# FPGA_SUP_CFG.net
KiCad netlist of a schematic drawn in Altium Designer
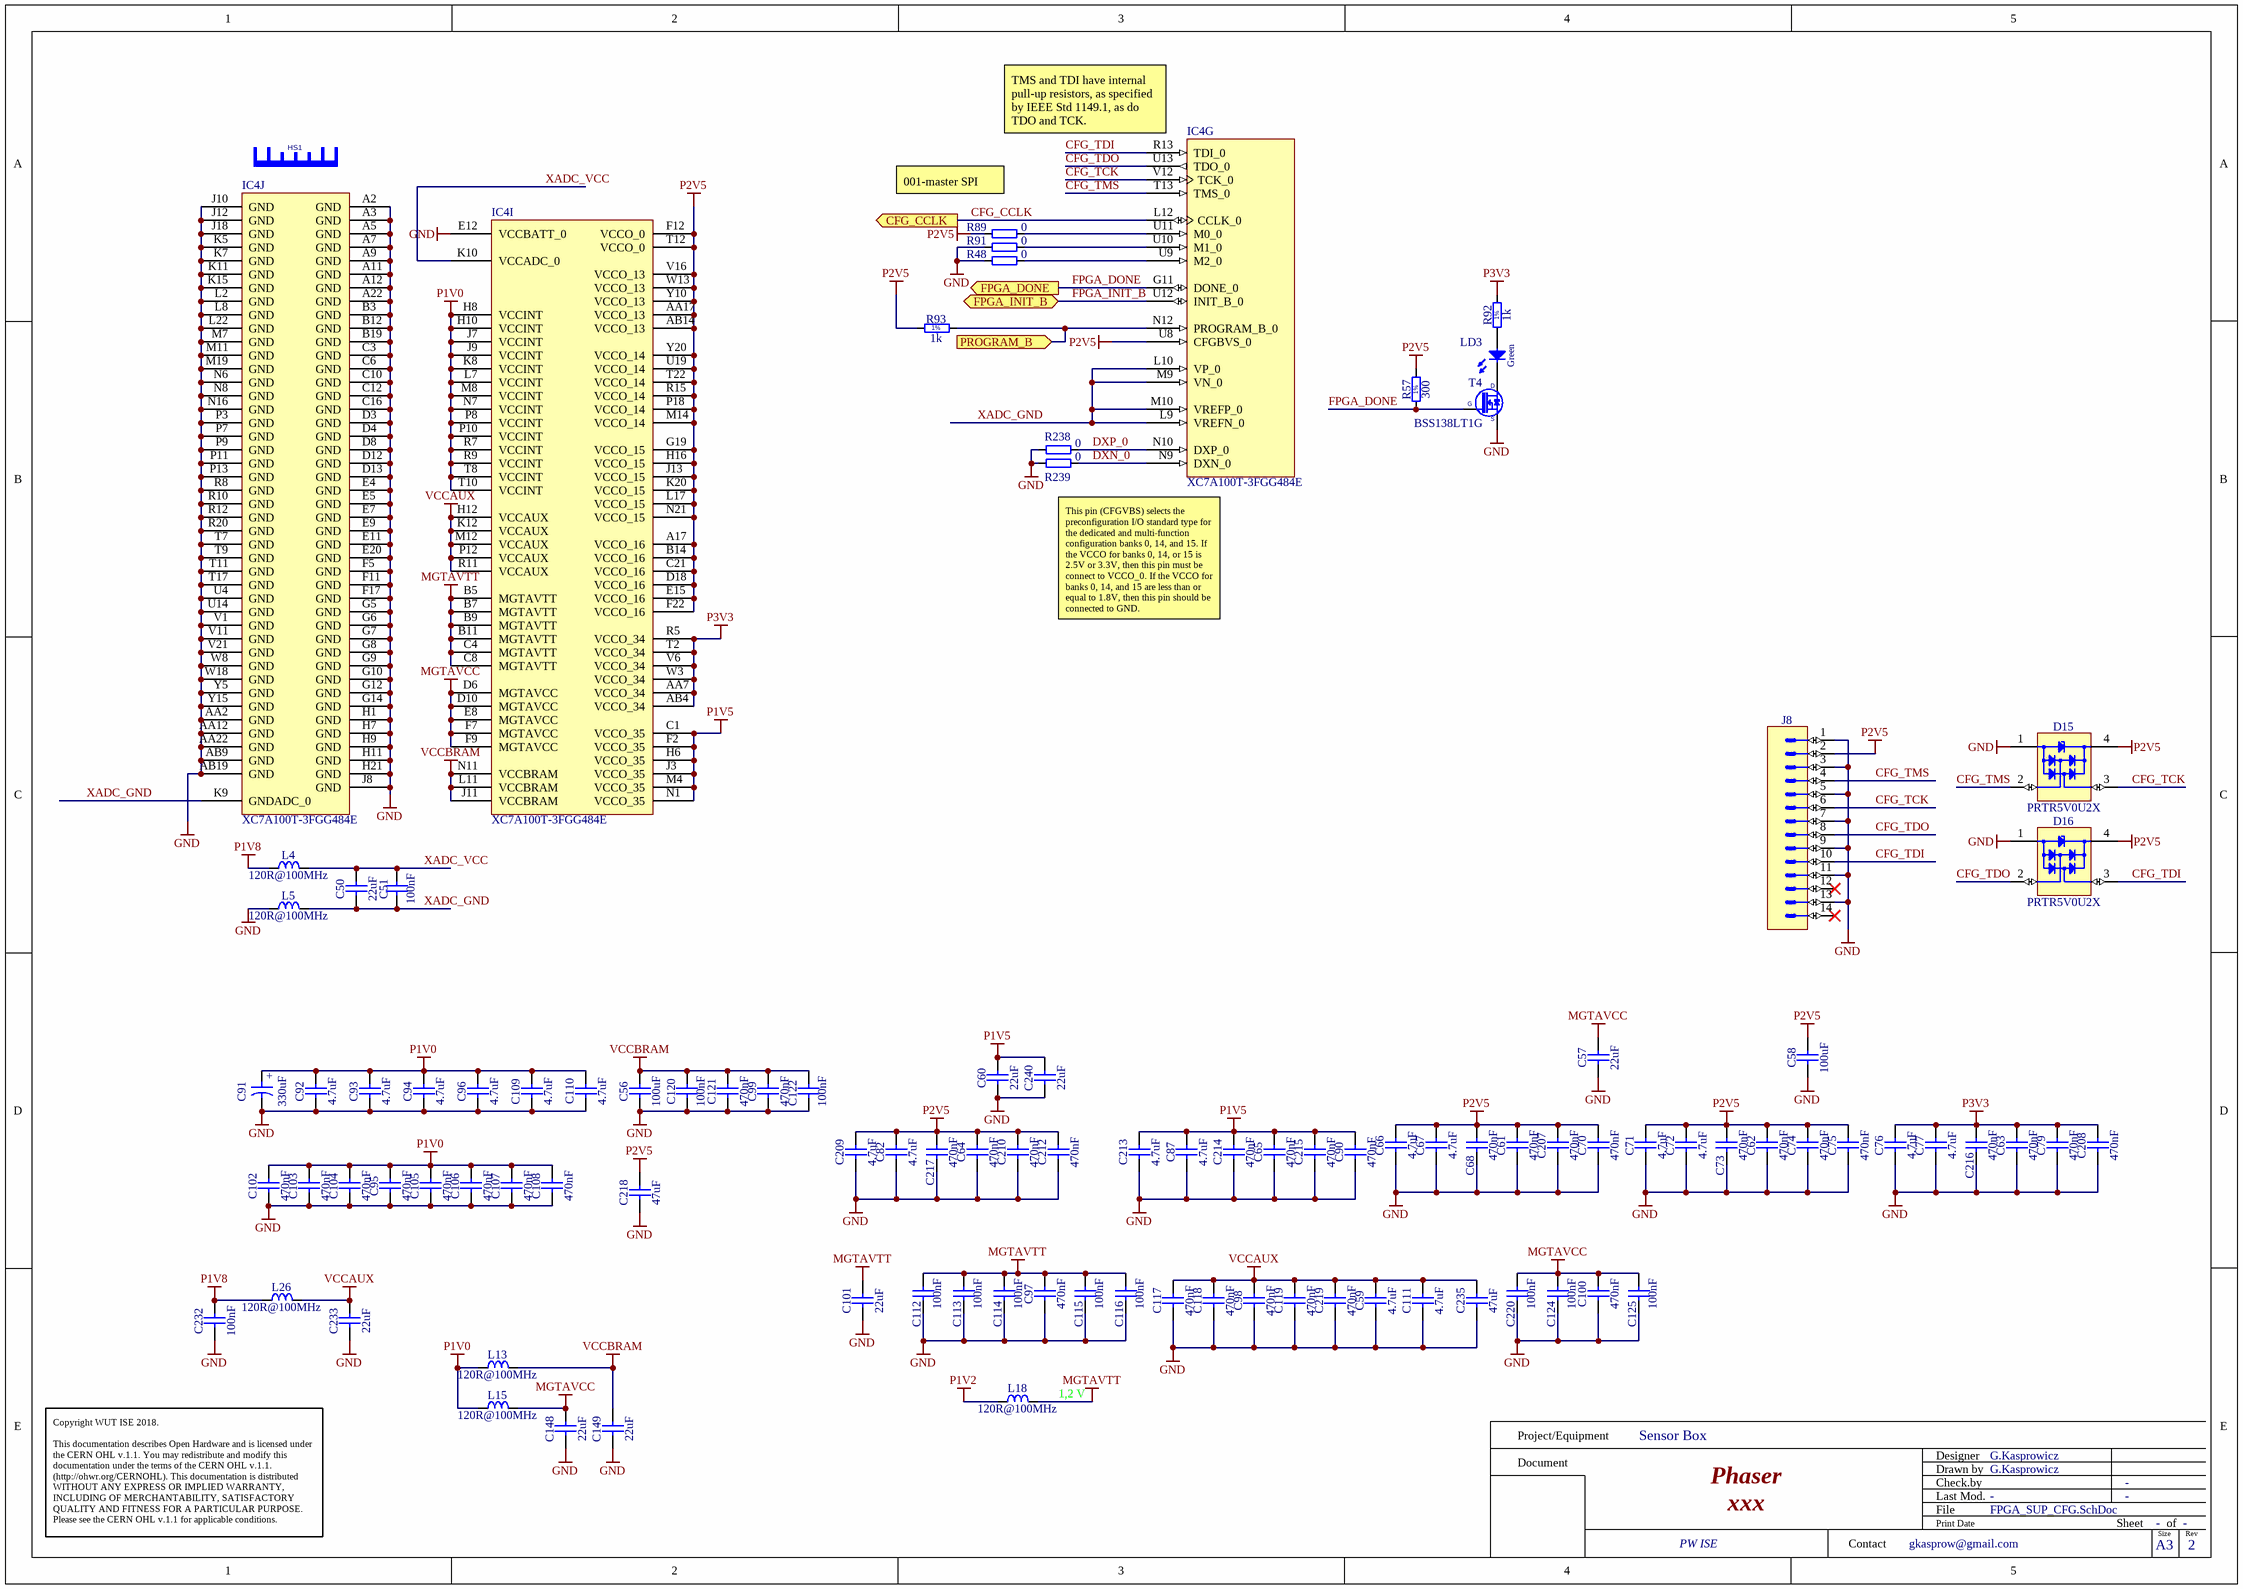
[diagram p0: FPGA_SUP_CFG.SchDoc]

(export (version "E")
  (design (tool "Eeschema 10.0.6"))
  (components
    (comp (ref "C50")
      (value "22uF")
      (footprint "CAPC1709X100N")
      (description "Non-polarised capacitor")
      (fields
        (field (name "PART NUMBER") "CC0603_22UF_6.3V_20%_X5R")
        (field (name "VOLTAGE") "6.3V")
        (field (name "AUTHOR") "CERN DEM JLC")
      )
      (libsource (lib "Capacitors") (part "Capacitor - non polarized"))
    )
    (comp (ref "C51")
      (value "100nF")
      (footprint "CAPC0603X33N")
      (description "Non-polarised capacitor")
      (fields
        (field (name "PART NUMBER") "CC0201_100NF_6.3V_10%_X5R")
        (field (name "VOLTAGE") "6.3V")
        (field (name "AUTHOR") "CERN DEM JLC")
      )
      (libsource (lib "Capacitors") (part "Capacitor - non polarized"))
    )
    (comp (ref "C56")
      (value "100uF")
      (footprint "CAPC3225X270N")
      (description "Non-polarised capacitor")
      (fields
        (field (name "PART NUMBER") "CC1210_100UF_6.3V_20%_X5R")
        (field (name "VOLTAGE") "6.3V")
        (field (name "AUTHOR") "CERN DEM JLC")
      )
      (libsource (lib "Capacitors") (part "Capacitor - non polarized"))
    )
    (comp (ref "C57")
      (value "22uF")
      (footprint "CAPC1709X100N")
      (description "Non-polarised capacitor")
      (fields
        (field (name "PART NUMBER") "CC0603_22UF_6.3V_20%_X5R")
        (field (name "VOLTAGE") "6.3V")
        (field (name "AUTHOR") "CERN DEM JLC")
      )
      (libsource (lib "Capacitors") (part "Capacitor - non polarized"))
    )
    (comp (ref "C58")
      (value "100uF")
      (footprint "CAPC3225X270N")
      (description "Non-polarised capacitor")
      (fields
        (field (name "PART NUMBER") "CC1210_100UF_6.3V_20%_X5R")
        (field (name "VOLTAGE") "6.3V")
        (field (name "AUTHOR") "CERN DEM JLC")
      )
      (libsource (lib "Capacitors") (part "Capacitor - non polarized"))
    )
    (comp (ref "C59")
      (value "4.7uF")
      (footprint "CAPC2012X135N")
      (description "Non-polarised capacitor")
      (fields
        (field (name "MANUFACTURER") "GENERIC")
        (field (name "PART NUMBER") "CC0805_4.7UF_10V_10%_X5R")
        (field (name "AUTHOR") "CERN DEM JLC")
      )
      (libsource (lib "Capacitors") (part "Capacitor - non polarized"))
    )
    (comp (ref "C60")
      (value "22uF")
      (footprint "CAPC1709X100N")
      (description "Non-polarised capacitor")
      (fields
        (field (name "PART NUMBER") "CC0603_22UF_6.3V_20%_X5R")
        (field (name "VOLTAGE") "6.3V")
        (field (name "AUTHOR") "CERN DEM JLC")
      )
      (libsource (lib "Capacitors") (part "Capacitor - non polarized"))
    )
    (comp (ref "C61")
      (value "470nF")
      (footprint "CAPC0603X33N")
      (description "Non-polarised capacitor")
      (fields
        (field (name "PART NUMBER") "CC0201_470NF_4V_20%_X5R")
        (field (name "VOLTAGE") "4V")
        (field (name "AUTHOR") "CERN DEM JLC")
      )
      (libsource (lib "Capacitors") (part "Capacitor - non polarized"))
    )
    (comp (ref "C62")
      (value "470nF")
      (footprint "CAPC0603X33N")
      (description "Non-polarised capacitor")
      (fields
        (field (name "PART NUMBER") "CC0201_470NF_4V_20%_X5R")
        (field (name "VOLTAGE") "4V")
        (field (name "AUTHOR") "CERN DEM JLC")
      )
      (libsource (lib "Capacitors") (part "Capacitor - non polarized"))
    )
    (comp (ref "C63")
      (value "470nF")
      (footprint "CAPC0603X33N")
      (description "Non-polarised capacitor")
      (fields
        (field (name "PART NUMBER") "CC0201_470NF_4V_20%_X5R")
        (field (name "VOLTAGE") "4V")
        (field (name "AUTHOR") "CERN DEM JLC")
      )
      (libsource (lib "Capacitors") (part "Capacitor - non polarized"))
    )
    (comp (ref "C64")
      (value "470nF")
      (footprint "CAPC0603X33N")
      (description "Non-polarised capacitor")
      (fields
        (field (name "PART NUMBER") "CC0201_470NF_4V_20%_X5R")
        (field (name "VOLTAGE") "4V")
        (field (name "AUTHOR") "CERN DEM JLC")
      )
      (libsource (lib "Capacitors") (part "Capacitor - non polarized"))
    )
    (comp (ref "C65")
      (value "470nF")
      (footprint "CAPC0603X33N")
      (description "Non-polarised capacitor")
      (fields
        (field (name "PART NUMBER") "CC0201_470NF_4V_20%_X5R")
        (field (name "VOLTAGE") "4V")
        (field (name "AUTHOR") "CERN DEM JLC")
      )
      (libsource (lib "Capacitors") (part "Capacitor - non polarized"))
    )
    (comp (ref "C66")
      (value "4.7uF")
      (footprint "CAPC2012X135N")
      (description "Non-polarised capacitor")
      (fields
        (field (name "MANUFACTURER") "GENERIC")
        (field (name "PART NUMBER") "CC0805_4.7UF_10V_10%_X5R")
        (field (name "AUTHOR") "CERN DEM JLC")
      )
      (libsource (lib "Capacitors") (part "Capacitor - non polarized"))
    )
    (comp (ref "C67")
      (value "4.7uF")
      (footprint "CAPC2012X135N")
      (description "Non-polarised capacitor")
      (fields
        (field (name "MANUFACTURER") "GENERIC")
        (field (name "PART NUMBER") "CC0805_4.7UF_10V_10%_X5R")
        (field (name "AUTHOR") "CERN DEM JLC")
      )
      (libsource (lib "Capacitors") (part "Capacitor - non polarized"))
    )
    (comp (ref "C68")
      (value "470nF")
      (footprint "CAPC0603X33N")
      (description "Non-polarised capacitor")
      (fields
        (field (name "PART NUMBER") "CC0201_470NF_4V_20%_X5R")
        (field (name "VOLTAGE") "4V")
        (field (name "AUTHOR") "CERN DEM JLC")
      )
      (libsource (lib "Capacitors") (part "Capacitor - non polarized"))
    )
    (comp (ref "C70")
      (value "470nF")
      (footprint "CAPC0603X33N")
      (description "Non-polarised capacitor")
      (fields
        (field (name "PART NUMBER") "CC0201_470NF_4V_20%_X5R")
        (field (name "VOLTAGE") "4V")
        (field (name "AUTHOR") "CERN DEM JLC")
      )
      (libsource (lib "Capacitors") (part "Capacitor - non polarized"))
    )
    (comp (ref "C71")
      (value "4.7uF")
      (footprint "CAPC2012X135N")
      (description "Non-polarised capacitor")
      (fields
        (field (name "MANUFACTURER") "GENERIC")
        (field (name "PART NUMBER") "CC0805_4.7UF_10V_10%_X5R")
        (field (name "AUTHOR") "CERN DEM JLC")
      )
      (libsource (lib "Capacitors") (part "Capacitor - non polarized"))
    )
    (comp (ref "C72")
      (value "4.7uF")
      (footprint "CAPC2012X135N")
      (description "Non-polarised capacitor")
      (fields
        (field (name "MANUFACTURER") "GENERIC")
        (field (name "PART NUMBER") "CC0805_4.7UF_10V_10%_X5R")
        (field (name "AUTHOR") "CERN DEM JLC")
      )
      (libsource (lib "Capacitors") (part "Capacitor - non polarized"))
    )
    (comp (ref "C73")
      (value "470nF")
      (footprint "CAPC0603X33N")
      (description "Non-polarised capacitor")
      (fields
        (field (name "PART NUMBER") "CC0201_470NF_4V_20%_X5R")
        (field (name "VOLTAGE") "4V")
        (field (name "AUTHOR") "CERN DEM JLC")
      )
      (libsource (lib "Capacitors") (part "Capacitor - non polarized"))
    )
    (comp (ref "C74")
      (value "470nF")
      (footprint "CAPC0603X33N")
      (description "Non-polarised capacitor")
      (fields
        (field (name "PART NUMBER") "CC0201_470NF_4V_20%_X5R")
        (field (name "VOLTAGE") "4V")
        (field (name "AUTHOR") "CERN DEM JLC")
      )
      (libsource (lib "Capacitors") (part "Capacitor - non polarized"))
    )
    (comp (ref "C75")
      (value "470nF")
      (footprint "CAPC0603X33N")
      (description "Non-polarised capacitor")
      (fields
        (field (name "PART NUMBER") "CC0201_470NF_4V_20%_X5R")
        (field (name "VOLTAGE") "4V")
        (field (name "AUTHOR") "CERN DEM JLC")
      )
      (libsource (lib "Capacitors") (part "Capacitor - non polarized"))
    )
    (comp (ref "C76")
      (value "4.7uF")
      (footprint "CAPC2012X135N")
      (description "Non-polarised capacitor")
      (fields
        (field (name "MANUFACTURER") "GENERIC")
        (field (name "PART NUMBER") "CC0805_4.7UF_10V_10%_X5R")
        (field (name "AUTHOR") "CERN DEM JLC")
      )
      (libsource (lib "Capacitors") (part "Capacitor - non polarized"))
    )
    (comp (ref "C77")
      (value "4.7uF")
      (footprint "CAPC2012X135N")
      (description "Non-polarised capacitor")
      (fields
        (field (name "MANUFACTURER") "GENERIC")
        (field (name "PART NUMBER") "CC0805_4.7UF_10V_10%_X5R")
        (field (name "AUTHOR") "CERN DEM JLC")
      )
      (libsource (lib "Capacitors") (part "Capacitor - non polarized"))
    )
    (comp (ref "C79")
      (value "470nF")
      (footprint "CAPC0603X33N")
      (description "Non-polarised capacitor")
      (fields
        (field (name "PART NUMBER") "CC0201_470NF_4V_20%_X5R")
        (field (name "VOLTAGE") "4V")
        (field (name "AUTHOR") "CERN DEM JLC")
      )
      (libsource (lib "Capacitors") (part "Capacitor - non polarized"))
    )
    (comp (ref "C82")
      (value "4.7uF")
      (footprint "CAPC2012X135N")
      (description "Non-polarised capacitor")
      (fields
        (field (name "MANUFACTURER") "GENERIC")
        (field (name "PART NUMBER") "CC0805_4.7UF_10V_10%_X5R")
        (field (name "AUTHOR") "CERN DEM JLC")
      )
      (libsource (lib "Capacitors") (part "Capacitor - non polarized"))
    )
    (comp (ref "C87")
      (value "4.7uF")
      (footprint "CAPC2012X135N")
      (description "Non-polarised capacitor")
      (fields
        (field (name "MANUFACTURER") "GENERIC")
        (field (name "PART NUMBER") "CC0805_4.7UF_10V_10%_X5R")
        (field (name "AUTHOR") "CERN DEM JLC")
      )
      (libsource (lib "Capacitors") (part "Capacitor - non polarized"))
    )
    (comp (ref "C90")
      (value "470nF")
      (footprint "CAPC0603X33N")
      (description "Non-polarised capacitor")
      (fields
        (field (name "PART NUMBER") "CC0201_470NF_4V_20%_X5R")
        (field (name "VOLTAGE") "4V")
        (field (name "AUTHOR") "CERN DEM JLC")
      )
      (libsource (lib "Capacitors") (part "Capacitor - non polarized"))
    )
    (comp (ref "C91")
      (value "330uF")
      (footprint "CAPMP7343X190N")
      (description "Polarised capacitor")
      (fields
        (field (name "PART NUMBER") "CTE7343-19_330UF_2.5V_20%_LESR0025_KEMET_T520")
        (field (name "VOLTAGE") "2.5V")
        (field (name "AUTHOR") "CERN DEM MR")
      )
      (libsource (lib "Capacitors") (part "Capacitor - polarized"))
    )
    (comp (ref "C92")
      (value "4.7uF")
      (footprint "CAPC2012X135N")
      (description "Non-polarised capacitor")
      (fields
        (field (name "MANUFACTURER") "GENERIC")
        (field (name "PART NUMBER") "CC0805_4.7UF_10V_10%_X5R")
        (field (name "AUTHOR") "CERN DEM JLC")
      )
      (libsource (lib "Capacitors") (part "Capacitor - non polarized"))
    )
    (comp (ref "C93")
      (value "4.7uF")
      (footprint "CAPC2012X135N")
      (description "Non-polarised capacitor")
      (fields
        (field (name "MANUFACTURER") "GENERIC")
        (field (name "PART NUMBER") "CC0805_4.7UF_10V_10%_X5R")
        (field (name "AUTHOR") "CERN DEM JLC")
      )
      (libsource (lib "Capacitors") (part "Capacitor - non polarized"))
    )
    (comp (ref "C94")
      (value "4.7uF")
      (footprint "CAPC2012X135N")
      (description "Non-polarised capacitor")
      (fields
        (field (name "MANUFACTURER") "GENERIC")
        (field (name "PART NUMBER") "CC0805_4.7UF_10V_10%_X5R")
        (field (name "AUTHOR") "CERN DEM JLC")
      )
      (libsource (lib "Capacitors") (part "Capacitor - non polarized"))
    )
    (comp (ref "C95")
      (value "470nF")
      (footprint "CAPC0603X33N")
      (description "Non-polarised capacitor")
      (fields
        (field (name "PART NUMBER") "CC0201_470NF_4V_20%_X5R")
        (field (name "VOLTAGE") "4V")
        (field (name "AUTHOR") "CERN DEM JLC")
      )
      (libsource (lib "Capacitors") (part "Capacitor - non polarized"))
    )
    (comp (ref "C96")
      (value "4.7uF")
      (footprint "CAPC2012X135N")
      (description "Non-polarised capacitor")
      (fields
        (field (name "MANUFACTURER") "GENERIC")
        (field (name "PART NUMBER") "CC0805_4.7UF_10V_10%_X5R")
        (field (name "AUTHOR") "CERN DEM JLC")
      )
      (libsource (lib "Capacitors") (part "Capacitor - non polarized"))
    )
    (comp (ref "C97")
      (value "470nF")
      (footprint "CAPC0603X33N")
      (description "Non-polarised capacitor")
      (fields
        (field (name "PART NUMBER") "CC0201_470NF_4V_20%_X5R")
        (field (name "VOLTAGE") "4V")
        (field (name "AUTHOR") "CERN DEM JLC")
      )
      (libsource (lib "Capacitors") (part "Capacitor - non polarized"))
    )
    (comp (ref "C98")
      (value "470nF")
      (footprint "CAPC0603X33N")
      (description "Non-polarised capacitor")
      (fields
        (field (name "PART NUMBER") "CC0201_470NF_4V_20%_X5R")
        (field (name "VOLTAGE") "4V")
        (field (name "AUTHOR") "CERN DEM JLC")
      )
      (libsource (lib "Capacitors") (part "Capacitor - non polarized"))
    )
    (comp (ref "C99")
      (value "470nF")
      (footprint "CAPC0603X33N")
      (description "Non-polarised capacitor")
      (fields
        (field (name "PART NUMBER") "CC0201_470NF_4V_20%_X5R")
        (field (name "VOLTAGE") "4V")
        (field (name "AUTHOR") "CERN DEM JLC")
      )
      (libsource (lib "Capacitors") (part "Capacitor - non polarized"))
    )
    (comp (ref "C100")
      (value "470nF")
      (footprint "CAPC0603X33N")
      (description "Non-polarised capacitor")
      (fields
        (field (name "PART NUMBER") "CC0201_470NF_4V_20%_X5R")
        (field (name "VOLTAGE") "4V")
        (field (name "AUTHOR") "CERN DEM JLC")
      )
      (libsource (lib "Capacitors") (part "Capacitor - non polarized"))
    )
    (comp (ref "C101")
      (value "22uF")
      (footprint "CAPC1709X100N")
      (description "Non-polarised capacitor")
      (fields
        (field (name "PART NUMBER") "CC0603_22UF_6.3V_20%_X5R")
        (field (name "VOLTAGE") "6.3V")
        (field (name "AUTHOR") "CERN DEM JLC")
      )
      (libsource (lib "Capacitors") (part "Capacitor - non polarized"))
    )
    (comp (ref "C102")
      (value "470nF")
      (footprint "CAPC0603X33N")
      (description "Non-polarised capacitor")
      (fields
        (field (name "PART NUMBER") "CC0201_470NF_4V_20%_X5R")
        (field (name "VOLTAGE") "4V")
        (field (name "AUTHOR") "CERN DEM JLC")
      )
      (libsource (lib "Capacitors") (part "Capacitor - non polarized"))
    )
    (comp (ref "C103")
      (value "470nF")
      (footprint "CAPC0603X33N")
      (description "Non-polarised capacitor")
      (fields
        (field (name "PART NUMBER") "CC0201_470NF_4V_20%_X5R")
        (field (name "VOLTAGE") "4V")
        (field (name "AUTHOR") "CERN DEM JLC")
      )
      (libsource (lib "Capacitors") (part "Capacitor - non polarized"))
    )
    (comp (ref "C104")
      (value "470nF")
      (footprint "CAPC0603X33N")
      (description "Non-polarised capacitor")
      (fields
        (field (name "PART NUMBER") "CC0201_470NF_4V_20%_X5R")
        (field (name "VOLTAGE") "4V")
        (field (name "AUTHOR") "CERN DEM JLC")
      )
      (libsource (lib "Capacitors") (part "Capacitor - non polarized"))
    )
    (comp (ref "C105")
      (value "470nF")
      (footprint "CAPC0603X33N")
      (description "Non-polarised capacitor")
      (fields
        (field (name "PART NUMBER") "CC0201_470NF_4V_20%_X5R")
        (field (name "VOLTAGE") "4V")
        (field (name "AUTHOR") "CERN DEM JLC")
      )
      (libsource (lib "Capacitors") (part "Capacitor - non polarized"))
    )
    (comp (ref "C106")
      (value "470nF")
      (footprint "CAPC0603X33N")
      (description "Non-polarised capacitor")
      (fields
        (field (name "PART NUMBER") "CC0201_470NF_4V_20%_X5R")
        (field (name "VOLTAGE") "4V")
        (field (name "AUTHOR") "CERN DEM JLC")
      )
      (libsource (lib "Capacitors") (part "Capacitor - non polarized"))
    )
    (comp (ref "C107")
      (value "470nF")
      (footprint "CAPC0603X33N")
      (description "Non-polarised capacitor")
      (fields
        (field (name "PART NUMBER") "CC0201_470NF_4V_20%_X5R")
        (field (name "VOLTAGE") "4V")
        (field (name "AUTHOR") "CERN DEM JLC")
      )
      (libsource (lib "Capacitors") (part "Capacitor - non polarized"))
    )
    (comp (ref "C108")
      (value "470nF")
      (footprint "CAPC0603X33N")
      (description "Non-polarised capacitor")
      (fields
        (field (name "PART NUMBER") "CC0201_470NF_4V_20%_X5R")
        (field (name "VOLTAGE") "4V")
        (field (name "AUTHOR") "CERN DEM JLC")
      )
      (libsource (lib "Capacitors") (part "Capacitor - non polarized"))
    )
    (comp (ref "C109")
      (value "4.7uF")
      (footprint "CAPC2012X135N")
      (description "Non-polarised capacitor")
      (fields
        (field (name "MANUFACTURER") "GENERIC")
        (field (name "PART NUMBER") "CC0805_4.7UF_10V_10%_X5R")
        (field (name "AUTHOR") "CERN DEM JLC")
      )
      (libsource (lib "Capacitors") (part "Capacitor - non polarized"))
    )
    (comp (ref "C110")
      (value "4.7uF")
      (footprint "CAPC2012X135N")
      (description "Non-polarised capacitor")
      (fields
        (field (name "MANUFACTURER") "GENERIC")
        (field (name "PART NUMBER") "CC0805_4.7UF_10V_10%_X5R")
        (field (name "AUTHOR") "CERN DEM JLC")
      )
      (libsource (lib "Capacitors") (part "Capacitor - non polarized"))
    )
    (comp (ref "C111")
      (value "4.7uF")
      (footprint "CAPC2012X135N")
      (description "Non-polarised capacitor")
      (fields
        (field (name "MANUFACTURER") "GENERIC")
        (field (name "PART NUMBER") "CC0805_4.7UF_10V_10%_X5R")
        (field (name "AUTHOR") "CERN DEM JLC")
      )
      (libsource (lib "Capacitors") (part "Capacitor - non polarized"))
    )
    (comp (ref "C112")
      (value "100nF")
      (footprint "CAPC0603X33N")
      (description "Non-polarised capacitor")
      (fields
        (field (name "PART NUMBER") "CC0201_100NF_6.3V_10%_X5R")
        (field (name "VOLTAGE") "6.3V")
        (field (name "AUTHOR") "CERN DEM JLC")
      )
      (libsource (lib "Capacitors") (part "Capacitor - non polarized"))
    )
    (comp (ref "C113")
      (value "100nF")
      (footprint "CAPC0603X33N")
      (description "Non-polarised capacitor")
      (fields
        (field (name "PART NUMBER") "CC0201_100NF_6.3V_10%_X5R")
        (field (name "VOLTAGE") "6.3V")
        (field (name "AUTHOR") "CERN DEM JLC")
      )
      (libsource (lib "Capacitors") (part "Capacitor - non polarized"))
    )
    (comp (ref "C114")
      (value "100nF")
      (footprint "CAPC0603X33N")
      (description "Non-polarised capacitor")
      (fields
        (field (name "PART NUMBER") "CC0201_100NF_6.3V_10%_X5R")
        (field (name "VOLTAGE") "6.3V")
        (field (name "AUTHOR") "CERN DEM JLC")
      )
      (libsource (lib "Capacitors") (part "Capacitor - non polarized"))
    )
    (comp (ref "C115")
      (value "100nF")
      (footprint "CAPC0603X33N")
      (description "Non-polarised capacitor")
      (fields
        (field (name "PART NUMBER") "CC0201_100NF_6.3V_10%_X5R")
        (field (name "VOLTAGE") "6.3V")
        (field (name "AUTHOR") "CERN DEM JLC")
      )
      (libsource (lib "Capacitors") (part "Capacitor - non polarized"))
    )
    (comp (ref "C116")
      (value "100nF")
      (footprint "CAPC0603X33N")
      (description "Non-polarised capacitor")
      (fields
        (field (name "PART NUMBER") "CC0201_100NF_6.3V_10%_X5R")
        (field (name "VOLTAGE") "6.3V")
        (field (name "AUTHOR") "CERN DEM JLC")
      )
      (libsource (lib "Capacitors") (part "Capacitor - non polarized"))
    )
    (comp (ref "C117")
      (value "470nF")
      (footprint "CAPC0603X33N")
      (description "Non-polarised capacitor")
      (fields
        (field (name "PART NUMBER") "CC0201_470NF_4V_20%_X5R")
        (field (name "VOLTAGE") "4V")
        (field (name "AUTHOR") "CERN DEM JLC")
      )
      (libsource (lib "Capacitors") (part "Capacitor - non polarized"))
    )
    (comp (ref "C118")
      (value "470nF")
      (footprint "CAPC0603X33N")
      (description "Non-polarised capacitor")
      (fields
        (field (name "PART NUMBER") "CC0201_470NF_4V_20%_X5R")
        (field (name "VOLTAGE") "4V")
        (field (name "AUTHOR") "CERN DEM JLC")
      )
      (libsource (lib "Capacitors") (part "Capacitor - non polarized"))
    )
    (comp (ref "C119")
      (value "470nF")
      (footprint "CAPC0603X33N")
      (description "Non-polarised capacitor")
      (fields
        (field (name "PART NUMBER") "CC0201_470NF_4V_20%_X5R")
        (field (name "VOLTAGE") "4V")
        (field (name "AUTHOR") "CERN DEM JLC")
      )
      (libsource (lib "Capacitors") (part "Capacitor - non polarized"))
    )
    (comp (ref "C120")
      (value "100nF")
      (footprint "CAPC0603X33N")
      (description "Non-polarised capacitor")
      (fields
        (field (name "PART NUMBER") "CC0201_100NF_6.3V_10%_X5R")
        (field (name "VOLTAGE") "6.3V")
        (field (name "AUTHOR") "CERN DEM JLC")
      )
      (libsource (lib "Capacitors") (part "Capacitor - non polarized"))
    )
    (comp (ref "C121")
      (value "470nF")
      (footprint "CAPC0603X33N")
      (description "Non-polarised capacitor")
      (fields
        (field (name "PART NUMBER") "CC0201_470NF_4V_20%_X5R")
        (field (name "VOLTAGE") "4V")
        (field (name "AUTHOR") "CERN DEM JLC")
      )
      (libsource (lib "Capacitors") (part "Capacitor - non polarized"))
    )
    (comp (ref "C122")
      (value "100nF")
      (footprint "CAPC0603X33N")
      (description "Non-polarised capacitor")
      (fields
        (field (name "PART NUMBER") "CC0201_100NF_6.3V_10%_X5R")
        (field (name "VOLTAGE") "6.3V")
        (field (name "AUTHOR") "CERN DEM JLC")
      )
      (libsource (lib "Capacitors") (part "Capacitor - non polarized"))
    )
    (comp (ref "C124")
      (value "100nF")
      (footprint "CAPC0603X33N")
      (description "Non-polarised capacitor")
      (fields
        (field (name "PART NUMBER") "CC0201_100NF_6.3V_10%_X5R")
        (field (name "VOLTAGE") "6.3V")
        (field (name "AUTHOR") "CERN DEM JLC")
      )
      (libsource (lib "Capacitors") (part "Capacitor - non polarized"))
    )
    (comp (ref "C125")
      (value "100nF")
      (footprint "CAPC0603X33N")
      (description "Non-polarised capacitor")
      (fields
        (field (name "PART NUMBER") "CC0201_100NF_6.3V_10%_X5R")
        (field (name "VOLTAGE") "6.3V")
        (field (name "AUTHOR") "CERN DEM JLC")
      )
      (libsource (lib "Capacitors") (part "Capacitor - non polarized"))
    )
    (comp (ref "C148")
      (value "22uF")
      (footprint "CAPC1709X100N")
      (description "Non-polarised capacitor")
      (fields
        (field (name "PART NUMBER") "CC0603_22UF_6.3V_20%_X5R")
        (field (name "VOLTAGE") "6.3V")
        (field (name "AUTHOR") "CERN DEM JLC")
      )
      (libsource (lib "Capacitors") (part "Capacitor - non polarized"))
    )
    (comp (ref "C149")
      (value "22uF")
      (footprint "CAPC1709X100N")
      (description "Non-polarised capacitor")
      (fields
        (field (name "PART NUMBER") "CC0603_22UF_6.3V_20%_X5R")
        (field (name "VOLTAGE") "6.3V")
        (field (name "AUTHOR") "CERN DEM JLC")
      )
      (libsource (lib "Capacitors") (part "Capacitor - non polarized"))
    )
    (comp (ref "C207")
      (value "470nF")
      (footprint "CAPC0603X33N")
      (description "Non-polarised capacitor")
      (fields
        (field (name "PART NUMBER") "CC0201_470NF_4V_20%_X5R")
        (field (name "VOLTAGE") "4V")
        (field (name "AUTHOR") "CERN DEM JLC")
      )
      (libsource (lib "Capacitors") (part "Capacitor - non polarized"))
    )
    (comp (ref "C208")
      (value "470nF")
      (footprint "CAPC0603X33N")
      (description "Non-polarised capacitor")
      (fields
        (field (name "PART NUMBER") "CC0201_470NF_4V_20%_X5R")
        (field (name "VOLTAGE") "4V")
        (field (name "AUTHOR") "CERN DEM JLC")
      )
      (libsource (lib "Capacitors") (part "Capacitor - non polarized"))
    )
    (comp (ref "C209")
      (value "4.7uF")
      (footprint "CAPC2012X135N")
      (description "Non-polarised capacitor")
      (fields
        (field (name "MANUFACTURER") "GENERIC")
        (field (name "PART NUMBER") "CC0805_4.7UF_10V_10%_X5R")
        (field (name "AUTHOR") "CERN DEM JLC")
      )
      (libsource (lib "Capacitors") (part "Capacitor - non polarized"))
    )
    (comp (ref "C210")
      (value "470nF")
      (footprint "CAPC0603X33N")
      (description "Non-polarised capacitor")
      (fields
        (field (name "PART NUMBER") "CC0201_470NF_4V_20%_X5R")
        (field (name "VOLTAGE") "4V")
        (field (name "AUTHOR") "CERN DEM JLC")
      )
      (libsource (lib "Capacitors") (part "Capacitor - non polarized"))
    )
    (comp (ref "C212")
      (value "470nF")
      (footprint "CAPC0603X33N")
      (description "Non-polarised capacitor")
      (fields
        (field (name "PART NUMBER") "CC0201_470NF_4V_20%_X5R")
        (field (name "VOLTAGE") "4V")
        (field (name "AUTHOR") "CERN DEM JLC")
      )
      (libsource (lib "Capacitors") (part "Capacitor - non polarized"))
    )
    (comp (ref "C213")
      (value "4.7uF")
      (footprint "CAPC2012X135N")
      (description "Non-polarised capacitor")
      (fields
        (field (name "MANUFACTURER") "GENERIC")
        (field (name "PART NUMBER") "CC0805_4.7UF_10V_10%_X5R")
        (field (name "AUTHOR") "CERN DEM JLC")
      )
      (libsource (lib "Capacitors") (part "Capacitor - non polarized"))
    )
    (comp (ref "C214")
      (value "470nF")
      (footprint "CAPC0603X33N")
      (description "Non-polarised capacitor")
      (fields
        (field (name "PART NUMBER") "CC0201_470NF_4V_20%_X5R")
        (field (name "VOLTAGE") "4V")
        (field (name "AUTHOR") "CERN DEM JLC")
      )
      (libsource (lib "Capacitors") (part "Capacitor - non polarized"))
    )
    (comp (ref "C215")
      (value "470nF")
      (footprint "CAPC0603X33N")
      (description "Non-polarised capacitor")
      (fields
        (field (name "PART NUMBER") "CC0201_470NF_4V_20%_X5R")
        (field (name "VOLTAGE") "4V")
        (field (name "AUTHOR") "CERN DEM JLC")
      )
      (libsource (lib "Capacitors") (part "Capacitor - non polarized"))
    )
    (comp (ref "C216")
      (value "470nF")
      (footprint "CAPC0603X33N")
      (description "Non-polarised capacitor")
      (fields
        (field (name "PART NUMBER") "CC0201_470NF_4V_20%_X5R")
        (field (name "VOLTAGE") "4V")
        (field (name "AUTHOR") "CERN DEM JLC")
      )
      (libsource (lib "Capacitors") (part "Capacitor - non polarized"))
    )
    (comp (ref "C217")
      (value "470nF")
      (footprint "CAPC0603X33N")
      (description "Non-polarised capacitor")
      (fields
        (field (name "PART NUMBER") "CC0201_470NF_4V_20%_X5R")
        (field (name "VOLTAGE") "4V")
        (field (name "AUTHOR") "CERN DEM JLC")
      )
      (libsource (lib "Capacitors") (part "Capacitor - non polarized"))
    )
    (comp (ref "C218")
      (value "47uF")
      (footprint "CAPC3225X270N")
      (description "Non-polarised capacitor")
      (fields
        (field (name "PART NUMBER") "CC1210_47UF_10V_10%_X7R")
        (field (name "VOLTAGE") "10V")
        (field (name "AUTHOR") "CERN DEM BC")
      )
      (libsource (lib "Capacitors") (part "Capacitor - non polarized"))
    )
    (comp (ref "C219")
      (value "470nF")
      (footprint "CAPC0603X33N")
      (description "Non-polarised capacitor")
      (fields
        (field (name "PART NUMBER") "CC0201_470NF_4V_20%_X5R")
        (field (name "VOLTAGE") "4V")
        (field (name "AUTHOR") "CERN DEM JLC")
      )
      (libsource (lib "Capacitors") (part "Capacitor - non polarized"))
    )
    (comp (ref "C220")
      (value "100nF")
      (footprint "CAPC0603X33N")
      (description "Non-polarised capacitor")
      (fields
        (field (name "PART NUMBER") "CC0201_100NF_6.3V_10%_X5R")
        (field (name "VOLTAGE") "6.3V")
        (field (name "AUTHOR") "CERN DEM JLC")
      )
      (libsource (lib "Capacitors") (part "Capacitor - non polarized"))
    )
    (comp (ref "C232")
      (value "100nF")
      (footprint "CAPC0603X33N")
      (description "Non-polarised capacitor")
      (fields
        (field (name "PART NUMBER") "CC0201_100NF_6.3V_10%_X5R")
        (field (name "VOLTAGE") "6.3V")
        (field (name "AUTHOR") "CERN DEM JLC")
      )
      (libsource (lib "Capacitors") (part "Capacitor - non polarized"))
    )
    (comp (ref "C233")
      (value "22uF")
      (footprint "CAPC1709X100N")
      (description "Non-polarised capacitor")
      (fields
        (field (name "PART NUMBER") "CC0603_22UF_6.3V_20%_X5R")
        (field (name "VOLTAGE") "6.3V")
        (field (name "AUTHOR") "CERN DEM JLC")
      )
      (libsource (lib "Capacitors") (part "Capacitor - non polarized"))
    )
    (comp (ref "C235")
      (value "47uF")
      (footprint "CAPC3225X270N")
      (description "Non-polarised capacitor")
      (fields
        (field (name "PART NUMBER") "CC1210_47UF_10V_10%_X7R")
        (field (name "VOLTAGE") "10V")
        (field (name "AUTHOR") "CERN DEM BC")
      )
      (libsource (lib "Capacitors") (part "Capacitor - non polarized"))
    )
    (comp (ref "C240")
      (value "22uF")
      (footprint "CAPC1709X100N")
      (description "Non-polarised capacitor")
      (fields
        (field (name "PART NUMBER") "CC0603_22UF_6.3V_20%_X5R")
        (field (name "VOLTAGE") "6.3V")
        (field (name "AUTHOR") "CERN DEM JLC")
      )
      (libsource (lib "Capacitors") (part "Capacitor - non polarized"))
    )
    (comp (ref "D15")
      (value "PRTR5V0U2X")
      (footprint "SOT190P230X110-4N")
      (description "Ultra Low Capacitance Double Rail-to-Rail ESD Protection Diode")
      (fields
        (field (name "VOLTAGE") "5.5V")
        (field (name "MANUFACTURER") "NXP SEMICONDUCTORS")
        (field (name "AUTHOR") "CERN DEM JLC")
      )
      (libsource (lib "ICs And Semiconductors") (part "PRTR5V0U2X"))
    )
    (comp (ref "D16")
      (value "PRTR5V0U2X")
      (footprint "SOT190P230X110-4N")
      (description "Ultra Low Capacitance Double Rail-to-Rail ESD Protection Diode")
      (fields
        (field (name "VOLTAGE") "5.5V")
        (field (name "MANUFACTURER") "NXP SEMICONDUCTORS")
        (field (name "AUTHOR") "CERN DEM JLC")
      )
      (libsource (lib "ICs And Semiconductors") (part "PRTR5V0U2X"))
    )
    (comp (ref "HS1")
      (value "RADIAN_FI23")
      (footprint "RADIAN_FI23")
      (description "Heat Sink Without Pad")
      (fields
        (field (name "MANUFACTURER") "Radian Thermal Products, Inc.")
        (field (name "MANUFACTURER PART NUMBER") "FI23+BU+T725")
      )
      (libsource (lib "Schlib1") (part "RADIAN_FI23"))
    )
    (comp (ref "IC4")
      (value "XC7A100T-3FGG484E")
      (footprint "FGG484")
      (description "Artix-7 FPGA, 285 User I/Os, 4 GTP, 484-Ball BGA, Speed Grade 3, Extended Grade, Pb-Free")
      (fields (field (name "GENERIC PART NUMBER") "XC7A100T") (field (name "MANUFACTURER") "Xilinx"))
      (libsource (lib "Altium Content Vault") (part "XC7A100T-3FGG484E"))
    )
    (comp (ref "J8")
      (value "Milli-Grid™")
      (footprint "MOLEX_87832-1420")
      (description "Connector 14 Male")
      (fields
        (field (name "PART NUMBER") "MOLEX_87832-1420")
        (field (name "MANUFACTURER") "MOLEX")
        (field (name "AUTHOR") "CERN DEM JLC")
      )
      (libsource (lib "Connectors") (part "Connector 14 Male"))
    )
    (comp (ref "L4")
      (value "120R@100MHz")
      (footprint "INDC1608X65N")
      (description "Inductor")
      (fields
        (field (name "PART NUMBER") "IND0603_MURATA_BLM18SG121TN1D")
        (field (name "POWER") "3A")
        (field (name "AUTHOR") "CERN DEM JLC")
      )
      (libsource (lib "Inductors & Transformers") (part "Inductor"))
    )
    (comp (ref "L5")
      (value "120R@100MHz")
      (footprint "INDC1608X65N")
      (description "Inductor")
      (fields
        (field (name "PART NUMBER") "IND0603_MURATA_BLM18SG121TN1D")
        (field (name "POWER") "3A")
        (field (name "AUTHOR") "CERN DEM JLC")
      )
      (libsource (lib "Inductors & Transformers") (part "Inductor"))
    )
    (comp (ref "L13")
      (value "120R@100MHz")
      (footprint "INDC1608X65N")
      (description "Inductor")
      (fields
        (field (name "PART NUMBER") "IND0603_MURATA_BLM18SG121TN1D")
        (field (name "POWER") "3A")
        (field (name "AUTHOR") "CERN DEM JLC")
      )
      (libsource (lib "Inductors & Transformers") (part "Inductor"))
    )
    (comp (ref "L15")
      (value "120R@100MHz")
      (footprint "INDC1608X65N")
      (description "Inductor")
      (fields
        (field (name "PART NUMBER") "IND0603_MURATA_BLM18SG121TN1D")
        (field (name "POWER") "3A")
        (field (name "AUTHOR") "CERN DEM JLC")
      )
      (libsource (lib "Inductors & Transformers") (part "Inductor"))
    )
    (comp (ref "L18")
      (value "120R@100MHz")
      (footprint "INDC1608X65N")
      (description "Inductor")
      (fields
        (field (name "PART NUMBER") "IND0603_MURATA_BLM18SG121TN1D")
        (field (name "POWER") "3A")
        (field (name "AUTHOR") "CERN DEM JLC")
      )
      (libsource (lib "Inductors & Transformers") (part "Inductor"))
    )
    (comp (ref "L26")
      (value "120R@100MHz")
      (footprint "INDC1608X65N")
      (description "Inductor")
      (fields
        (field (name "PART NUMBER") "IND0603_MURATA_BLM18SG121TN1D")
        (field (name "POWER") "3A")
        (field (name "AUTHOR") "CERN DEM JLC")
      )
      (libsource (lib "Inductors & Transformers") (part "Inductor"))
    )
    (comp (ref "LD3")
      (value "Green")
      (footprint "LED_KINGBRIGHT_KPH-1608CGCK")
      (description "LED Green 1C 2A")
      (fields
        (field (name "MANUFACTURER PART NUMBER") "KPH-1608CGCK")
        (field (name "PART NUMBER") "LED_KINGBRIGHT_KPH-1608CGCK")
        (field (name "AUTHOR") "CERN DEM JLC")
      )
      (libsource (lib "ICs And Semiconductors") (part "LED Green 1C 2A"))
    )
    (comp (ref "R48")
      (value "0")
      (footprint "RESC1005X40N")
      (description "Resistor")
      (fields
        (field (name "PART NUMBER") "R0402_0R_JUMPER")
        (field (name "MANUFACTURER") "GENERIC")
        (field (name "AUTHOR") "CERN DEM JLC")
      )
      (libsource (lib "Resistors") (part "Resistor"))
    )
    (comp (ref "R57")
      (value "300")
      (footprint "RESC1005X40N")
      (description "Resistor - 1%")
      (fields
        (field (name "PART NUMBER") "R0402_300R_1%_0.0625W_100PPM")
        (field (name "POWER") "0.0625W")
        (field (name "AUTHOR") "CERN DEM JLC")
      )
      (libsource (lib "Resistors") (part "Resistor - 1%"))
    )
    (comp (ref "R89")
      (value "0")
      (footprint "RESC1005X40N")
      (description "Resistor")
      (fields
        (field (name "PART NUMBER") "R0402_0R_JUMPER")
        (field (name "MANUFACTURER") "GENERIC")
        (field (name "AUTHOR") "CERN DEM JLC")
      )
      (libsource (lib "Resistors") (part "Resistor"))
    )
    (comp (ref "R91")
      (value "0")
      (footprint "RESC1005X40N")
      (description "Resistor")
      (fields
        (field (name "PART NUMBER") "R0402_0R_JUMPER")
        (field (name "MANUFACTURER") "GENERIC")
        (field (name "AUTHOR") "CERN DEM JLC")
      )
      (libsource (lib "Resistors") (part "Resistor"))
    )
    (comp (ref "R92")
      (value "1k")
      (footprint "RESC1005X40N")
      (description "Resistor - 1%")
      (fields
        (field (name "PART NUMBER") "R0402_1K_1%_0.0625W_100PPM")
        (field (name "POWER") "0.0625W")
        (field (name "AUTHOR") "CERN DEM JLC")
      )
      (libsource (lib "Resistors") (part "Resistor - 1%"))
    )
    (comp (ref "R93")
      (value "1k")
      (footprint "RESC1005X40N")
      (description "Resistor - 1%")
      (fields
        (field (name "PART NUMBER") "R0402_1K_1%_0.0625W_100PPM")
        (field (name "POWER") "0.0625W")
        (field (name "AUTHOR") "CERN DEM JLC")
      )
      (libsource (lib "Resistors") (part "Resistor - 1%"))
    )
    (comp (ref "R238")
      (value "0")
      (footprint "RESC1005X40N")
      (description "Resistor")
      (fields
        (field (name "PART NUMBER") "R0402_0R_JUMPER")
        (field (name "MANUFACTURER") "GENERIC")
        (field (name "AUTHOR") "CERN DEM JLC")
      )
      (libsource (lib "Resistors") (part "Resistor"))
    )
    (comp (ref "R239")
      (value "0")
      (footprint "RESC1005X40N")
      (description "Resistor")
      (fields
        (field (name "PART NUMBER") "R0402_0R_JUMPER")
        (field (name "MANUFACTURER") "GENERIC")
        (field (name "AUTHOR") "CERN DEM JLC")
      )
      (libsource (lib "Resistors") (part "Resistor"))
    )
    (comp (ref "T4")
      (value "BSS138LT1G")
      (footprint "SOT95P240X110-3N")
      (description "N-CHANNEL MOSFET WITH DIODE")
      (fields (field (name "MANUFACTURER") "ON SEMICONDUCTOR") (field (name "AUTHOR") "CERN DEM JLC"))
      (libsource (lib "ICs And Semiconductors") (part "N-MOSFET-D 1G 2S 3D"))
    )
  )
  (nets
    (net (code "1") (name "/CFG_CCLK") (class "Default")
      (node (ref "IC4") (pin "L12") (pinfunction "CCLK_0_L12") (pintype "bidirectional"))
    )
    (net (code "2") (name "/CFG_TCK") (class "Default")
      (node (ref "D15") (pin "3") (pinfunction "I/O2_3") (pintype "bidirectional"))
      (node (ref "IC4") (pin "V12") (pinfunction "TCK_0_V12") (pintype "input"))
      (node (ref "J8") (pin "6") (pinfunction "6_6") (pintype "bidirectional"))
    )
    (net (code "3") (name "/CFG_TDI") (class "Default")
      (node (ref "D16") (pin "3") (pinfunction "I/O2_3") (pintype "bidirectional"))
      (node (ref "IC4") (pin "R13") (pinfunction "TDI_0_R13") (pintype "input"))
      (node (ref "J8") (pin "10") (pinfunction "10_10") (pintype "bidirectional"))
    )
    (net (code "4") (name "/CFG_TDO") (class "Default")
      (node (ref "D16") (pin "2") (pinfunction "I/O1_2") (pintype "bidirectional"))
      (node (ref "IC4") (pin "U13") (pinfunction "TDO_0_U13") (pintype "output"))
      (node (ref "J8") (pin "8") (pinfunction "8_8") (pintype "bidirectional"))
    )
    (net (code "5") (name "/CFG_TMS") (class "Default")
      (node (ref "D15") (pin "2") (pinfunction "I/O1_2") (pintype "bidirectional"))
      (node (ref "IC4") (pin "T13") (pinfunction "TMS_0_T13") (pintype "input"))
      (node (ref "J8") (pin "4") (pinfunction "4_4") (pintype "bidirectional"))
    )
    (net (code "6") (name "/DXN_0") (class "Default")
      (node (ref "IC4") (pin "N9") (pinfunction "DXN_0_N9") (pintype "input"))
      (node (ref "R239") (pin "2") (pinfunction "2_2") (pintype "passive"))
    )
    (net (code "7") (name "/DXP_0") (class "Default")
      (node (ref "IC4") (pin "N10") (pinfunction "DXP_0_N10") (pintype "input"))
      (node (ref "R238") (pin "2") (pinfunction "2_2") (pintype "passive"))
    )
    (net (code "8") (name "/FPGA_DONE") (class "Default")
      (node (ref "IC4") (pin "G11") (pinfunction "DONE_0_G11") (pintype "bidirectional"))
      (node (ref "R57") (pin "1") (pinfunction "1_1") (pintype "passive"))
      (node (ref "T4") (pin "1") (pinfunction "G_1") (pintype "passive"))
    )
    (net (code "9") (name "/FPGA_INIT_B") (class "Default")
      (node (ref "IC4") (pin "U12") (pinfunction "INIT_B_0_U12") (pintype "bidirectional"))
    )
    (net (code "10") (name "/PROGRAM_B") (class "Default")
      (node (ref "IC4") (pin "N12") (pinfunction "PROGRAM_B_0_N12") (pintype "input"))
      (node (ref "R93") (pin "2") (pinfunction "2_2") (pintype "passive"))
    )
    (net (code "11") (name "/XADC_GND") (class "Default")
      (node (ref "C50") (pin "1") (pinfunction "1_1") (pintype "passive"))
      (node (ref "C51") (pin "1") (pinfunction "1_1") (pintype "passive"))
      (node (ref "IC4") (pin "K9") (pinfunction "GNDADC_0_K9") (pintype "power_in"))
      (node (ref "IC4") (pin "L10") (pinfunction "VP_0_L10") (pintype "input"))
      (node (ref "IC4") (pin "L9") (pinfunction "VREFN_0_L9") (pintype "input"))
      (node (ref "IC4") (pin "M10") (pinfunction "VREFP_0_M10") (pintype "input"))
      (node (ref "IC4") (pin "M9") (pinfunction "VN_0_M9") (pintype "input"))
      (node (ref "L5") (pin "2") (pinfunction "2_2") (pintype "passive"))
    )
    (net (code "12") (name "/XADC_VCC") (class "Default")
      (node (ref "C50") (pin "2") (pinfunction "2_2") (pintype "passive"))
      (node (ref "C51") (pin "2") (pinfunction "2_2") (pintype "passive"))
      (node (ref "IC4") (pin "K10") (pinfunction "VCCADC_0_K10") (pintype "power_in"))
      (node (ref "L4") (pin "2") (pinfunction "2_2") (pintype "passive"))
    )
    (net (code "13") (name "GND") (class "Default")
      (node (ref "C100") (pin "1") (pinfunction "1_1") (pintype "passive"))
      (node (ref "C101") (pin "1") (pinfunction "1_1") (pintype "passive"))
      (node (ref "C102") (pin "1") (pinfunction "1_1") (pintype "passive"))
      (node (ref "C103") (pin "1") (pinfunction "1_1") (pintype "passive"))
      (node (ref "C104") (pin "1") (pinfunction "1_1") (pintype "passive"))
      (node (ref "C105") (pin "1") (pinfunction "1_1") (pintype "passive"))
      (node (ref "C106") (pin "1") (pinfunction "1_1") (pintype "passive"))
      (node (ref "C107") (pin "1") (pinfunction "1_1") (pintype "passive"))
      (node (ref "C108") (pin "1") (pinfunction "1_1") (pintype "passive"))
      (node (ref "C109") (pin "1") (pinfunction "1_1") (pintype "passive"))
      (node (ref "C110") (pin "1") (pinfunction "1_1") (pintype "passive"))
      (node (ref "C111") (pin "1") (pinfunction "1_1") (pintype "passive"))
      (node (ref "C112") (pin "1") (pinfunction "1_1") (pintype "passive"))
      (node (ref "C113") (pin "1") (pinfunction "1_1") (pintype "passive"))
      (node (ref "C114") (pin "1") (pinfunction "1_1") (pintype "passive"))
      (node (ref "C115") (pin "1") (pinfunction "1_1") (pintype "passive"))
      (node (ref "C116") (pin "1") (pinfunction "1_1") (pintype "passive"))
      (node (ref "C117") (pin "1") (pinfunction "1_1") (pintype "passive"))
      (node (ref "C118") (pin "1") (pinfunction "1_1") (pintype "passive"))
      (node (ref "C119") (pin "1") (pinfunction "1_1") (pintype "passive"))
      (node (ref "C120") (pin "1") (pinfunction "1_1") (pintype "passive"))
      (node (ref "C121") (pin "1") (pinfunction "1_1") (pintype "passive"))
      (node (ref "C122") (pin "1") (pinfunction "1_1") (pintype "passive"))
      (node (ref "C124") (pin "1") (pinfunction "1_1") (pintype "passive"))
      (node (ref "C125") (pin "1") (pinfunction "1_1") (pintype "passive"))
      (node (ref "C148") (pin "1") (pinfunction "1_1") (pintype "passive"))
      (node (ref "C149") (pin "1") (pinfunction "1_1") (pintype "passive"))
      (node (ref "C207") (pin "1") (pinfunction "1_1") (pintype "passive"))
      (node (ref "C208") (pin "1") (pinfunction "1_1") (pintype "passive"))
      (node (ref "C209") (pin "1") (pinfunction "1_1") (pintype "passive"))
      (node (ref "C210") (pin "1") (pinfunction "1_1") (pintype "passive"))
      (node (ref "C212") (pin "1") (pinfunction "1_1") (pintype "passive"))
      (node (ref "C213") (pin "1") (pinfunction "1_1") (pintype "passive"))
      (node (ref "C214") (pin "1") (pinfunction "1_1") (pintype "passive"))
      (node (ref "C215") (pin "1") (pinfunction "1_1") (pintype "passive"))
      (node (ref "C216") (pin "1") (pinfunction "1_1") (pintype "passive"))
      (node (ref "C217") (pin "1") (pinfunction "1_1") (pintype "passive"))
      (node (ref "C218") (pin "1") (pinfunction "1_1") (pintype "passive"))
      (node (ref "C219") (pin "1") (pinfunction "1_1") (pintype "passive"))
      (node (ref "C220") (pin "1") (pinfunction "1_1") (pintype "passive"))
      (node (ref "C232") (pin "1") (pinfunction "1_1") (pintype "passive"))
      (node (ref "C233") (pin "1") (pinfunction "1_1") (pintype "passive"))
      (node (ref "C235") (pin "1") (pinfunction "1_1") (pintype "passive"))
      (node (ref "C240") (pin "1") (pinfunction "1_1") (pintype "passive"))
      (node (ref "C56") (pin "1") (pinfunction "1_1") (pintype "passive"))
      (node (ref "C57") (pin "1") (pinfunction "1_1") (pintype "passive"))
      (node (ref "C58") (pin "1") (pinfunction "1_1") (pintype "passive"))
      (node (ref "C59") (pin "1") (pinfunction "1_1") (pintype "passive"))
      (node (ref "C60") (pin "1") (pinfunction "1_1") (pintype "passive"))
      (node (ref "C61") (pin "1") (pinfunction "1_1") (pintype "passive"))
      (node (ref "C62") (pin "1") (pinfunction "1_1") (pintype "passive"))
      (node (ref "C63") (pin "1") (pinfunction "1_1") (pintype "passive"))
      (node (ref "C64") (pin "1") (pinfunction "1_1") (pintype "passive"))
      (node (ref "C65") (pin "1") (pinfunction "1_1") (pintype "passive"))
      (node (ref "C66") (pin "1") (pinfunction "1_1") (pintype "passive"))
      (node (ref "C67") (pin "1") (pinfunction "1_1") (pintype "passive"))
      (node (ref "C68") (pin "1") (pinfunction "1_1") (pintype "passive"))
      (node (ref "C70") (pin "1") (pinfunction "1_1") (pintype "passive"))
      (node (ref "C71") (pin "1") (pinfunction "1_1") (pintype "passive"))
      (node (ref "C72") (pin "1") (pinfunction "1_1") (pintype "passive"))
      (node (ref "C73") (pin "1") (pinfunction "1_1") (pintype "passive"))
      (node (ref "C74") (pin "1") (pinfunction "1_1") (pintype "passive"))
      (node (ref "C75") (pin "1") (pinfunction "1_1") (pintype "passive"))
      (node (ref "C76") (pin "1") (pinfunction "1_1") (pintype "passive"))
      (node (ref "C77") (pin "1") (pinfunction "1_1") (pintype "passive"))
      (node (ref "C79") (pin "1") (pinfunction "1_1") (pintype "passive"))
      (node (ref "C82") (pin "1") (pinfunction "1_1") (pintype "passive"))
      (node (ref "C87") (pin "1") (pinfunction "1_1") (pintype "passive"))
      (node (ref "C90") (pin "1") (pinfunction "1_1") (pintype "passive"))
      (node (ref "C91") (pin "2") (pinfunction "2_2") (pintype "passive"))
      (node (ref "C92") (pin "1") (pinfunction "1_1") (pintype "passive"))
      (node (ref "C93") (pin "1") (pinfunction "1_1") (pintype "passive"))
      (node (ref "C94") (pin "1") (pinfunction "1_1") (pintype "passive"))
      (node (ref "C95") (pin "1") (pinfunction "1_1") (pintype "passive"))
      (node (ref "C96") (pin "1") (pinfunction "1_1") (pintype "passive"))
      (node (ref "C97") (pin "1") (pinfunction "1_1") (pintype "passive"))
      (node (ref "C98") (pin "1") (pinfunction "1_1") (pintype "passive"))
      (node (ref "C99") (pin "1") (pinfunction "1_1") (pintype "passive"))
      (node (ref "D15") (pin "1") (pinfunction "GND_1") (pintype "power_in"))
      (node (ref "D16") (pin "1") (pinfunction "GND_1") (pintype "power_in"))
      (node (ref "IC4") (pin "A11") (pinfunction "GND_A11") (pintype "power_in"))
      (node (ref "IC4") (pin "A12") (pinfunction "GND_A12") (pintype "power_in"))
      (node (ref "IC4") (pin "A2") (pinfunction "GND_A2") (pintype "power_in"))
      (node (ref "IC4") (pin "A22") (pinfunction "GND_A22") (pintype "power_in"))
      (node (ref "IC4") (pin "A3") (pinfunction "GND_A3") (pintype "power_in"))
      (node (ref "IC4") (pin "A5") (pinfunction "GND_A5") (pintype "power_in"))
      (node (ref "IC4") (pin "A7") (pinfunction "GND_A7") (pintype "power_in"))
      (node (ref "IC4") (pin "A9") (pinfunction "GND_A9") (pintype "power_in"))
      (node (ref "IC4") (pin "AA12") (pinfunction "GND_AA12") (pintype "power_in"))
      (node (ref "IC4") (pin "AA2") (pinfunction "GND_AA2") (pintype "power_in"))
      (node (ref "IC4") (pin "AA22") (pinfunction "GND_AA22") (pintype "power_in"))
      (node (ref "IC4") (pin "AB19") (pinfunction "GND_AB19") (pintype "power_in"))
      (node (ref "IC4") (pin "AB9") (pinfunction "GND_AB9") (pintype "power_in"))
      (node (ref "IC4") (pin "B12") (pinfunction "GND_B12") (pintype "power_in"))
      (node (ref "IC4") (pin "B19") (pinfunction "GND_B19") (pintype "power_in"))
      (node (ref "IC4") (pin "B3") (pinfunction "GND_B3") (pintype "power_in"))
      (node (ref "IC4") (pin "C10") (pinfunction "GND_C10") (pintype "power_in"))
      (node (ref "IC4") (pin "C12") (pinfunction "GND_C12") (pintype "power_in"))
      (node (ref "IC4") (pin "C16") (pinfunction "GND_C16") (pintype "power_in"))
      (node (ref "IC4") (pin "C3") (pinfunction "GND_C3") (pintype "power_in"))
      (node (ref "IC4") (pin "C6") (pinfunction "GND_C6") (pintype "power_in"))
      (node (ref "IC4") (pin "D12") (pinfunction "GND_D12") (pintype "power_in"))
      (node (ref "IC4") (pin "D13") (pinfunction "GND_D13") (pintype "power_in"))
      (node (ref "IC4") (pin "D3") (pinfunction "GND_D3") (pintype "power_in"))
      (node (ref "IC4") (pin "D4") (pinfunction "GND_D4") (pintype "power_in"))
      (node (ref "IC4") (pin "D8") (pinfunction "GND_D8") (pintype "power_in"))
      (node (ref "IC4") (pin "E11") (pinfunction "GND_E11") (pintype "power_in"))
      (node (ref "IC4") (pin "E12") (pinfunction "VCCBATT_0_E12") (pintype "power_in"))
      (node (ref "IC4") (pin "E20") (pinfunction "GND_E20") (pintype "power_in"))
      (node (ref "IC4") (pin "E4") (pinfunction "GND_E4") (pintype "power_in"))
      (node (ref "IC4") (pin "E5") (pinfunction "GND_E5") (pintype "power_in"))
      (node (ref "IC4") (pin "E7") (pinfunction "GND_E7") (pintype "power_in"))
      (node (ref "IC4") (pin "E9") (pinfunction "GND_E9") (pintype "power_in"))
      (node (ref "IC4") (pin "F11") (pinfunction "GND_F11") (pintype "power_in"))
      (node (ref "IC4") (pin "F17") (pinfunction "GND_F17") (pintype "power_in"))
      (node (ref "IC4") (pin "F5") (pinfunction "GND_F5") (pintype "power_in"))
      (node (ref "IC4") (pin "G10") (pinfunction "GND_G10") (pintype "power_in"))
      (node (ref "IC4") (pin "G12") (pinfunction "GND_G12") (pintype "power_in"))
      (node (ref "IC4") (pin "G14") (pinfunction "GND_G14") (pintype "power_in"))
      (node (ref "IC4") (pin "G5") (pinfunction "GND_G5") (pintype "power_in"))
      (node (ref "IC4") (pin "G6") (pinfunction "GND_G6") (pintype "power_in"))
      (node (ref "IC4") (pin "G7") (pinfunction "GND_G7") (pintype "power_in"))
      (node (ref "IC4") (pin "G8") (pinfunction "GND_G8") (pintype "power_in"))
      (node (ref "IC4") (pin "G9") (pinfunction "GND_G9") (pintype "power_in"))
      (node (ref "IC4") (pin "H1") (pinfunction "GND_H1") (pintype "power_in"))
      (node (ref "IC4") (pin "H11") (pinfunction "GND_H11") (pintype "power_in"))
      (node (ref "IC4") (pin "H21") (pinfunction "GND_H21") (pintype "power_in"))
      (node (ref "IC4") (pin "H7") (pinfunction "GND_H7") (pintype "power_in"))
      (node (ref "IC4") (pin "H9") (pinfunction "GND_H9") (pintype "power_in"))
      (node (ref "IC4") (pin "J10") (pinfunction "GND_J10") (pintype "power_in"))
      (node (ref "IC4") (pin "J12") (pinfunction "GND_J12") (pintype "power_in"))
      (node (ref "IC4") (pin "J18") (pinfunction "GND_J18") (pintype "power_in"))
      (node (ref "IC4") (pin "J8") (pinfunction "GND_J8") (pintype "power_in"))
      (node (ref "IC4") (pin "K11") (pinfunction "GND_K11") (pintype "power_in"))
      (node (ref "IC4") (pin "K15") (pinfunction "GND_K15") (pintype "power_in"))
      (node (ref "IC4") (pin "K5") (pinfunction "GND_K5") (pintype "power_in"))
      (node (ref "IC4") (pin "K7") (pinfunction "GND_K7") (pintype "power_in"))
      (node (ref "IC4") (pin "L2") (pinfunction "GND_L2") (pintype "power_in"))
      (node (ref "IC4") (pin "L22") (pinfunction "GND_L22") (pintype "power_in"))
      (node (ref "IC4") (pin "L8") (pinfunction "GND_L8") (pintype "power_in"))
      (node (ref "IC4") (pin "M11") (pinfunction "GND_M11") (pintype "power_in"))
      (node (ref "IC4") (pin "M19") (pinfunction "GND_M19") (pintype "power_in"))
      (node (ref "IC4") (pin "M7") (pinfunction "GND_M7") (pintype "power_in"))
      (node (ref "IC4") (pin "N16") (pinfunction "GND_N16") (pintype "power_in"))
      (node (ref "IC4") (pin "N6") (pinfunction "GND_N6") (pintype "power_in"))
      (node (ref "IC4") (pin "N8") (pinfunction "GND_N8") (pintype "power_in"))
      (node (ref "IC4") (pin "P11") (pinfunction "GND_P11") (pintype "power_in"))
      (node (ref "IC4") (pin "P13") (pinfunction "GND_P13") (pintype "power_in"))
      (node (ref "IC4") (pin "P3") (pinfunction "GND_P3") (pintype "power_in"))
      (node (ref "IC4") (pin "P7") (pinfunction "GND_P7") (pintype "power_in"))
      (node (ref "IC4") (pin "P9") (pinfunction "GND_P9") (pintype "power_in"))
      (node (ref "IC4") (pin "R10") (pinfunction "GND_R10") (pintype "power_in"))
      (node (ref "IC4") (pin "R12") (pinfunction "GND_R12") (pintype "power_in"))
      (node (ref "IC4") (pin "R20") (pinfunction "GND_R20") (pintype "power_in"))
      (node (ref "IC4") (pin "R8") (pinfunction "GND_R8") (pintype "power_in"))
      (node (ref "IC4") (pin "T11") (pinfunction "GND_T11") (pintype "power_in"))
      (node (ref "IC4") (pin "T17") (pinfunction "GND_T17") (pintype "power_in"))
      (node (ref "IC4") (pin "T7") (pinfunction "GND_T7") (pintype "power_in"))
      (node (ref "IC4") (pin "T9") (pinfunction "GND_T9") (pintype "power_in"))
      (node (ref "IC4") (pin "U14") (pinfunction "GND_U14") (pintype "power_in"))
      (node (ref "IC4") (pin "U4") (pinfunction "GND_U4") (pintype "power_in"))
      (node (ref "IC4") (pin "V1") (pinfunction "GND_V1") (pintype "power_in"))
      (node (ref "IC4") (pin "V11") (pinfunction "GND_V11") (pintype "power_in"))
      (node (ref "IC4") (pin "V21") (pinfunction "GND_V21") (pintype "power_in"))
      (node (ref "IC4") (pin "W18") (pinfunction "GND_W18") (pintype "power_in"))
      (node (ref "IC4") (pin "W8") (pinfunction "GND_W8") (pintype "power_in"))
      (node (ref "IC4") (pin "Y15") (pinfunction "GND_Y15") (pintype "power_in"))
      (node (ref "IC4") (pin "Y5") (pinfunction "GND_Y5") (pintype "power_in"))
      (node (ref "J8") (pin "1") (pinfunction "1_1") (pintype "bidirectional"))
      (node (ref "J8") (pin "11") (pinfunction "11_11") (pintype "bidirectional"))
      (node (ref "J8") (pin "13") (pinfunction "13_13") (pintype "bidirectional"))
      (node (ref "J8") (pin "3") (pinfunction "3_3") (pintype "bidirectional"))
      (node (ref "J8") (pin "5") (pinfunction "5_5") (pintype "bidirectional"))
      (node (ref "J8") (pin "7") (pinfunction "7_7") (pintype "bidirectional"))
      (node (ref "J8") (pin "9") (pinfunction "9_9") (pintype "bidirectional"))
      (node (ref "L5") (pin "1") (pinfunction "1_1") (pintype "passive"))
      (node (ref "R238") (pin "1") (pinfunction "1_1") (pintype "passive"))
      (node (ref "R239") (pin "1") (pinfunction "1_1") (pintype "passive"))
      (node (ref "R48") (pin "1") (pinfunction "1_1") (pintype "passive"))
      (node (ref "R91") (pin "1") (pinfunction "1_1") (pintype "passive"))
      (node (ref "T4") (pin "2") (pinfunction "S_2") (pintype "passive"))
    )
    (net (code "14") (name "MGTAVCC") (class "Default")
      (node (ref "C100") (pin "2") (pinfunction "2_2") (pintype "passive"))
      (node (ref "C124") (pin "2") (pinfunction "2_2") (pintype "passive"))
      (node (ref "C125") (pin "2") (pinfunction "2_2") (pintype "passive"))
      (node (ref "C148") (pin "2") (pinfunction "2_2") (pintype "passive"))
      (node (ref "C220") (pin "2") (pinfunction "2_2") (pintype "passive"))
      (node (ref "C57") (pin "2") (pinfunction "2_2") (pintype "passive"))
      (node (ref "IC4") (pin "D10") (pinfunction "MGTAVCC_D10") (pintype "power_in"))
      (node (ref "IC4") (pin "D6") (pinfunction "MGTAVCC_D6") (pintype "power_in"))
      (node (ref "IC4") (pin "E8") (pinfunction "MGTAVCC_E8") (pintype "power_in"))
      (node (ref "IC4") (pin "F7") (pinfunction "MGTAVCC_F7") (pintype "power_in"))
      (node (ref "IC4") (pin "F9") (pinfunction "MGTAVCC_F9") (pintype "power_in"))
      (node (ref "L15") (pin "2") (pinfunction "2_2") (pintype "passive"))
    )
    (net (code "15") (name "MGTAVTT") (class "Default")
      (node (ref "C101") (pin "2") (pinfunction "2_2") (pintype "passive"))
      (node (ref "C112") (pin "2") (pinfunction "2_2") (pintype "passive"))
      (node (ref "C113") (pin "2") (pinfunction "2_2") (pintype "passive"))
      (node (ref "C114") (pin "2") (pinfunction "2_2") (pintype "passive"))
      (node (ref "C115") (pin "2") (pinfunction "2_2") (pintype "passive"))
      (node (ref "C116") (pin "2") (pinfunction "2_2") (pintype "passive"))
      (node (ref "C97") (pin "2") (pinfunction "2_2") (pintype "passive"))
      (node (ref "IC4") (pin "B11") (pinfunction "MGTAVTT_B11") (pintype "power_in"))
      (node (ref "IC4") (pin "B5") (pinfunction "MGTAVTT_B5") (pintype "power_in"))
      (node (ref "IC4") (pin "B7") (pinfunction "MGTAVTT_B7") (pintype "power_in"))
      (node (ref "IC4") (pin "B9") (pinfunction "MGTAVTT_B9") (pintype "power_in"))
      (node (ref "IC4") (pin "C4") (pinfunction "MGTAVTT_C4") (pintype "power_in"))
      (node (ref "IC4") (pin "C8") (pinfunction "MGTAVTT_C8") (pintype "power_in"))
      (node (ref "L18") (pin "2") (pinfunction "2_2") (pintype "passive"))
    )
    (net (code "16") (name "Net-(IC4G-M0_0)") (class "Default")
      (node (ref "IC4") (pin "U11") (pinfunction "M0_0_U11") (pintype "input"))
      (node (ref "R89") (pin "2") (pinfunction "2_2") (pintype "passive"))
    )
    (net (code "17") (name "Net-(IC4G-M1_0)") (class "Default")
      (node (ref "IC4") (pin "U10") (pinfunction "M1_0_U10") (pintype "input"))
      (node (ref "R91") (pin "2") (pinfunction "2_2") (pintype "passive"))
    )
    (net (code "18") (name "Net-(IC4G-M2_0)") (class "Default")
      (node (ref "IC4") (pin "U9") (pinfunction "M2_0_U9") (pintype "input"))
      (node (ref "R48") (pin "2") (pinfunction "2_2") (pintype "passive"))
    )
    (net (code "19") (name "Net-(LD3-A)") (class "Default")
      (node (ref "LD3") (pin "2") (pinfunction "A_2") (pintype "passive"))
      (node (ref "R92") (pin "1") (pinfunction "1_1") (pintype "passive"))
    )
    (net (code "20") (name "Net-(LD3-C)") (class "Default")
      (node (ref "LD3") (pin "1") (pinfunction "C_1") (pintype "passive"))
      (node (ref "T4") (pin "3") (pinfunction "D_3") (pintype "passive"))
    )
    (net (code "21") (name "P1V0") (class "Default")
      (node (ref "C102") (pin "2") (pinfunction "2_2") (pintype "passive"))
      (node (ref "C103") (pin "2") (pinfunction "2_2") (pintype "passive"))
      (node (ref "C104") (pin "2") (pinfunction "2_2") (pintype "passive"))
      (node (ref "C105") (pin "2") (pinfunction "2_2") (pintype "passive"))
      (node (ref "C106") (pin "2") (pinfunction "2_2") (pintype "passive"))
      (node (ref "C107") (pin "2") (pinfunction "2_2") (pintype "passive"))
      (node (ref "C108") (pin "2") (pinfunction "2_2") (pintype "passive"))
      (node (ref "C109") (pin "2") (pinfunction "2_2") (pintype "passive"))
      (node (ref "C110") (pin "2") (pinfunction "2_2") (pintype "passive"))
      (node (ref "C91") (pin "1") (pinfunction "1_1") (pintype "passive"))
      (node (ref "C92") (pin "2") (pinfunction "2_2") (pintype "passive"))
      (node (ref "C93") (pin "2") (pinfunction "2_2") (pintype "passive"))
      (node (ref "C94") (pin "2") (pinfunction "2_2") (pintype "passive"))
      (node (ref "C95") (pin "2") (pinfunction "2_2") (pintype "passive"))
      (node (ref "C96") (pin "2") (pinfunction "2_2") (pintype "passive"))
      (node (ref "IC4") (pin "H10") (pinfunction "VCCINT_H10") (pintype "power_in"))
      (node (ref "IC4") (pin "H8") (pinfunction "VCCINT_H8") (pintype "power_in"))
      (node (ref "IC4") (pin "J7") (pinfunction "VCCINT_J7") (pintype "power_in"))
      (node (ref "IC4") (pin "J9") (pinfunction "VCCINT_J9") (pintype "power_in"))
      (node (ref "IC4") (pin "K8") (pinfunction "VCCINT_K8") (pintype "power_in"))
      (node (ref "IC4") (pin "L7") (pinfunction "VCCINT_L7") (pintype "power_in"))
      (node (ref "IC4") (pin "M8") (pinfunction "VCCINT_M8") (pintype "power_in"))
      (node (ref "IC4") (pin "N7") (pinfunction "VCCINT_N7") (pintype "power_in"))
      (node (ref "IC4") (pin "P10") (pinfunction "VCCINT_P10") (pintype "power_in"))
      (node (ref "IC4") (pin "P8") (pinfunction "VCCINT_P8") (pintype "power_in"))
      (node (ref "IC4") (pin "R7") (pinfunction "VCCINT_R7") (pintype "power_in"))
      (node (ref "IC4") (pin "R9") (pinfunction "VCCINT_R9") (pintype "power_in"))
      (node (ref "IC4") (pin "T10") (pinfunction "VCCINT_T10") (pintype "power_in"))
      (node (ref "IC4") (pin "T8") (pinfunction "VCCINT_T8") (pintype "power_in"))
      (node (ref "L13") (pin "1") (pinfunction "1_1") (pintype "passive"))
      (node (ref "L15") (pin "1") (pinfunction "1_1") (pintype "passive"))
    )
    (net (code "22") (name "P1V2") (class "Default")
      (node (ref "L18") (pin "1") (pinfunction "1_1") (pintype "passive"))
    )
    (net (code "23") (name "P1V5") (class "Default")
      (node (ref "C213") (pin "2") (pinfunction "2_2") (pintype "passive"))
      (node (ref "C214") (pin "2") (pinfunction "2_2") (pintype "passive"))
      (node (ref "C215") (pin "2") (pinfunction "2_2") (pintype "passive"))
      (node (ref "C240") (pin "2") (pinfunction "2_2") (pintype "passive"))
      (node (ref "C60") (pin "2") (pinfunction "2_2") (pintype "passive"))
      (node (ref "C65") (pin "2") (pinfunction "2_2") (pintype "passive"))
      (node (ref "C87") (pin "2") (pinfunction "2_2") (pintype "passive"))
      (node (ref "C90") (pin "2") (pinfunction "2_2") (pintype "passive"))
      (node (ref "IC4") (pin "C1") (pinfunction "VCCO_35_C1") (pintype "power_in"))
      (node (ref "IC4") (pin "F2") (pinfunction "VCCO_35_F2") (pintype "power_in"))
      (node (ref "IC4") (pin "H6") (pinfunction "VCCO_35_H6") (pintype "power_in"))
      (node (ref "IC4") (pin "J3") (pinfunction "VCCO_35_J3") (pintype "power_in"))
      (node (ref "IC4") (pin "M4") (pinfunction "VCCO_35_M4") (pintype "power_in"))
      (node (ref "IC4") (pin "N1") (pinfunction "VCCO_35_N1") (pintype "power_in"))
    )
    (net (code "24") (name "P1V8") (class "Default")
      (node (ref "C232") (pin "2") (pinfunction "2_2") (pintype "passive"))
      (node (ref "L26") (pin "1") (pinfunction "1_1") (pintype "passive"))
      (node (ref "L4") (pin "1") (pinfunction "1_1") (pintype "passive"))
    )
    (net (code "25") (name "P2V5") (class "Default")
      (node (ref "C207") (pin "2") (pinfunction "2_2") (pintype "passive"))
      (node (ref "C209") (pin "2") (pinfunction "2_2") (pintype "passive"))
      (node (ref "C210") (pin "2") (pinfunction "2_2") (pintype "passive"))
      (node (ref "C212") (pin "2") (pinfunction "2_2") (pintype "passive"))
      (node (ref "C217") (pin "2") (pinfunction "2_2") (pintype "passive"))
      (node (ref "C218") (pin "2") (pinfunction "2_2") (pintype "passive"))
      (node (ref "C58") (pin "2") (pinfunction "2_2") (pintype "passive"))
      (node (ref "C61") (pin "2") (pinfunction "2_2") (pintype "passive"))
      (node (ref "C62") (pin "2") (pinfunction "2_2") (pintype "passive"))
      (node (ref "C64") (pin "2") (pinfunction "2_2") (pintype "passive"))
      (node (ref "C66") (pin "2") (pinfunction "2_2") (pintype "passive"))
      (node (ref "C67") (pin "2") (pinfunction "2_2") (pintype "passive"))
      (node (ref "C68") (pin "2") (pinfunction "2_2") (pintype "passive"))
      (node (ref "C70") (pin "2") (pinfunction "2_2") (pintype "passive"))
      (node (ref "C71") (pin "2") (pinfunction "2_2") (pintype "passive"))
      (node (ref "C72") (pin "2") (pinfunction "2_2") (pintype "passive"))
      (node (ref "C73") (pin "2") (pinfunction "2_2") (pintype "passive"))
      (node (ref "C74") (pin "2") (pinfunction "2_2") (pintype "passive"))
      (node (ref "C75") (pin "2") (pinfunction "2_2") (pintype "passive"))
      (node (ref "C82") (pin "2") (pinfunction "2_2") (pintype "passive"))
      (node (ref "D15") (pin "4") (pinfunction "VCC_4") (pintype "power_in"))
      (node (ref "D16") (pin "4") (pinfunction "VCC_4") (pintype "power_in"))
      (node (ref "IC4") (pin "A17") (pinfunction "VCCO_16_A17") (pintype "power_in"))
      (node (ref "IC4") (pin "AA17") (pinfunction "VCCO_13_AA17") (pintype "power_in"))
      (node (ref "IC4") (pin "AB14") (pinfunction "VCCO_13_AB14") (pintype "power_in"))
      (node (ref "IC4") (pin "B14") (pinfunction "VCCO_16_B14") (pintype "power_in"))
      (node (ref "IC4") (pin "C21") (pinfunction "VCCO_16_C21") (pintype "power_in"))
      (node (ref "IC4") (pin "D18") (pinfunction "VCCO_16_D18") (pintype "power_in"))
      (node (ref "IC4") (pin "E15") (pinfunction "VCCO_16_E15") (pintype "power_in"))
      (node (ref "IC4") (pin "F12") (pinfunction "VCCO_0_F12") (pintype "power_in"))
      (node (ref "IC4") (pin "F22") (pinfunction "VCCO_16_F22") (pintype "power_in"))
      (node (ref "IC4") (pin "G19") (pinfunction "VCCO_15_G19") (pintype "power_in"))
      (node (ref "IC4") (pin "H16") (pinfunction "VCCO_15_H16") (pintype "power_in"))
      (node (ref "IC4") (pin "J13") (pinfunction "VCCO_15_J13") (pintype "power_in"))
      (node (ref "IC4") (pin "K20") (pinfunction "VCCO_15_K20") (pintype "power_in"))
      (node (ref "IC4") (pin "L17") (pinfunction "VCCO_15_L17") (pintype "power_in"))
      (node (ref "IC4") (pin "M14") (pinfunction "VCCO_14_M14") (pintype "power_in"))
      (node (ref "IC4") (pin "N21") (pinfunction "VCCO_15_N21") (pintype "power_in"))
      (node (ref "IC4") (pin "P18") (pinfunction "VCCO_14_P18") (pintype "power_in"))
      (node (ref "IC4") (pin "R15") (pinfunction "VCCO_14_R15") (pintype "power_in"))
      (node (ref "IC4") (pin "T12") (pinfunction "VCCO_0_T12") (pintype "power_in"))
      (node (ref "IC4") (pin "T22") (pinfunction "VCCO_14_T22") (pintype "power_in"))
      (node (ref "IC4") (pin "U19") (pinfunction "VCCO_14_U19") (pintype "power_in"))
      (node (ref "IC4") (pin "U8") (pinfunction "CFGBVS_0_U8") (pintype "input"))
      (node (ref "IC4") (pin "V16") (pinfunction "VCCO_13_V16") (pintype "power_in"))
      (node (ref "IC4") (pin "W13") (pinfunction "VCCO_13_W13") (pintype "power_in"))
      (node (ref "IC4") (pin "Y10") (pinfunction "VCCO_13_Y10") (pintype "power_in"))
      (node (ref "IC4") (pin "Y20") (pinfunction "VCCO_14_Y20") (pintype "power_in"))
      (node (ref "J8") (pin "2") (pinfunction "2_2") (pintype "bidirectional"))
      (node (ref "R57") (pin "2") (pinfunction "2_2") (pintype "passive"))
      (node (ref "R89") (pin "1") (pinfunction "1_1") (pintype "passive"))
      (node (ref "R93") (pin "1") (pinfunction "1_1") (pintype "passive"))
    )
    (net (code "26") (name "P3V3") (class "Default")
      (node (ref "C208") (pin "2") (pinfunction "2_2") (pintype "passive"))
      (node (ref "C216") (pin "2") (pinfunction "2_2") (pintype "passive"))
      (node (ref "C63") (pin "2") (pinfunction "2_2") (pintype "passive"))
      (node (ref "C76") (pin "2") (pinfunction "2_2") (pintype "passive"))
      (node (ref "C77") (pin "2") (pinfunction "2_2") (pintype "passive"))
      (node (ref "C79") (pin "2") (pinfunction "2_2") (pintype "passive"))
      (node (ref "IC4") (pin "AA7") (pinfunction "VCCO_34_AA7") (pintype "power_in"))
      (node (ref "IC4") (pin "AB4") (pinfunction "VCCO_34_AB4") (pintype "power_in"))
      (node (ref "IC4") (pin "R5") (pinfunction "VCCO_34_R5") (pintype "power_in"))
      (node (ref "IC4") (pin "T2") (pinfunction "VCCO_34_T2") (pintype "power_in"))
      (node (ref "IC4") (pin "V6") (pinfunction "VCCO_34_V6") (pintype "power_in"))
      (node (ref "IC4") (pin "W3") (pinfunction "VCCO_34_W3") (pintype "power_in"))
      (node (ref "R92") (pin "2") (pinfunction "2_2") (pintype "passive"))
    )
    (net (code "27") (name "VCCAUX") (class "Default")
      (node (ref "C111") (pin "2") (pinfunction "2_2") (pintype "passive"))
      (node (ref "C117") (pin "2") (pinfunction "2_2") (pintype "passive"))
      (node (ref "C118") (pin "2") (pinfunction "2_2") (pintype "passive"))
      (node (ref "C119") (pin "2") (pinfunction "2_2") (pintype "passive"))
      (node (ref "C219") (pin "2") (pinfunction "2_2") (pintype "passive"))
      (node (ref "C233") (pin "2") (pinfunction "2_2") (pintype "passive"))
      (node (ref "C235") (pin "2") (pinfunction "2_2") (pintype "passive"))
      (node (ref "C59") (pin "2") (pinfunction "2_2") (pintype "passive"))
      (node (ref "C98") (pin "2") (pinfunction "2_2") (pintype "passive"))
      (node (ref "IC4") (pin "H12") (pinfunction "VCCAUX_H12") (pintype "power_in"))
      (node (ref "IC4") (pin "K12") (pinfunction "VCCAUX_K12") (pintype "power_in"))
      (node (ref "IC4") (pin "M12") (pinfunction "VCCAUX_M12") (pintype "power_in"))
      (node (ref "IC4") (pin "P12") (pinfunction "VCCAUX_P12") (pintype "power_in"))
      (node (ref "IC4") (pin "R11") (pinfunction "VCCAUX_R11") (pintype "power_in"))
      (node (ref "L26") (pin "2") (pinfunction "2_2") (pintype "passive"))
    )
    (net (code "28") (name "VCCBRAM") (class "Default")
      (node (ref "C120") (pin "2") (pinfunction "2_2") (pintype "passive"))
      (node (ref "C121") (pin "2") (pinfunction "2_2") (pintype "passive"))
      (node (ref "C122") (pin "2") (pinfunction "2_2") (pintype "passive"))
      (node (ref "C149") (pin "2") (pinfunction "2_2") (pintype "passive"))
      (node (ref "C56") (pin "2") (pinfunction "2_2") (pintype "passive"))
      (node (ref "C99") (pin "2") (pinfunction "2_2") (pintype "passive"))
      (node (ref "IC4") (pin "J11") (pinfunction "VCCBRAM_J11") (pintype "power_in"))
      (node (ref "IC4") (pin "L11") (pinfunction "VCCBRAM_L11") (pintype "power_in"))
      (node (ref "IC4") (pin "N11") (pinfunction "VCCBRAM_N11") (pintype "power_in"))
      (node (ref "L13") (pin "2") (pinfunction "2_2") (pintype "passive"))
    )
    (net (code "29") (name "unconnected-(J8-Pad12)") (class "Default")
      (node (ref "J8") (pin "12") (pinfunction "12_12") (pintype "bidirectional+no_connect"))
    )
    (net (code "30") (name "unconnected-(J8-Pad14)") (class "Default")
      (node (ref "J8") (pin "14") (pinfunction "14_14") (pintype "bidirectional+no_connect"))
    )
  )
)
